# Drivers.net
KiCad netlist of a schematic drawn in Altium Designer
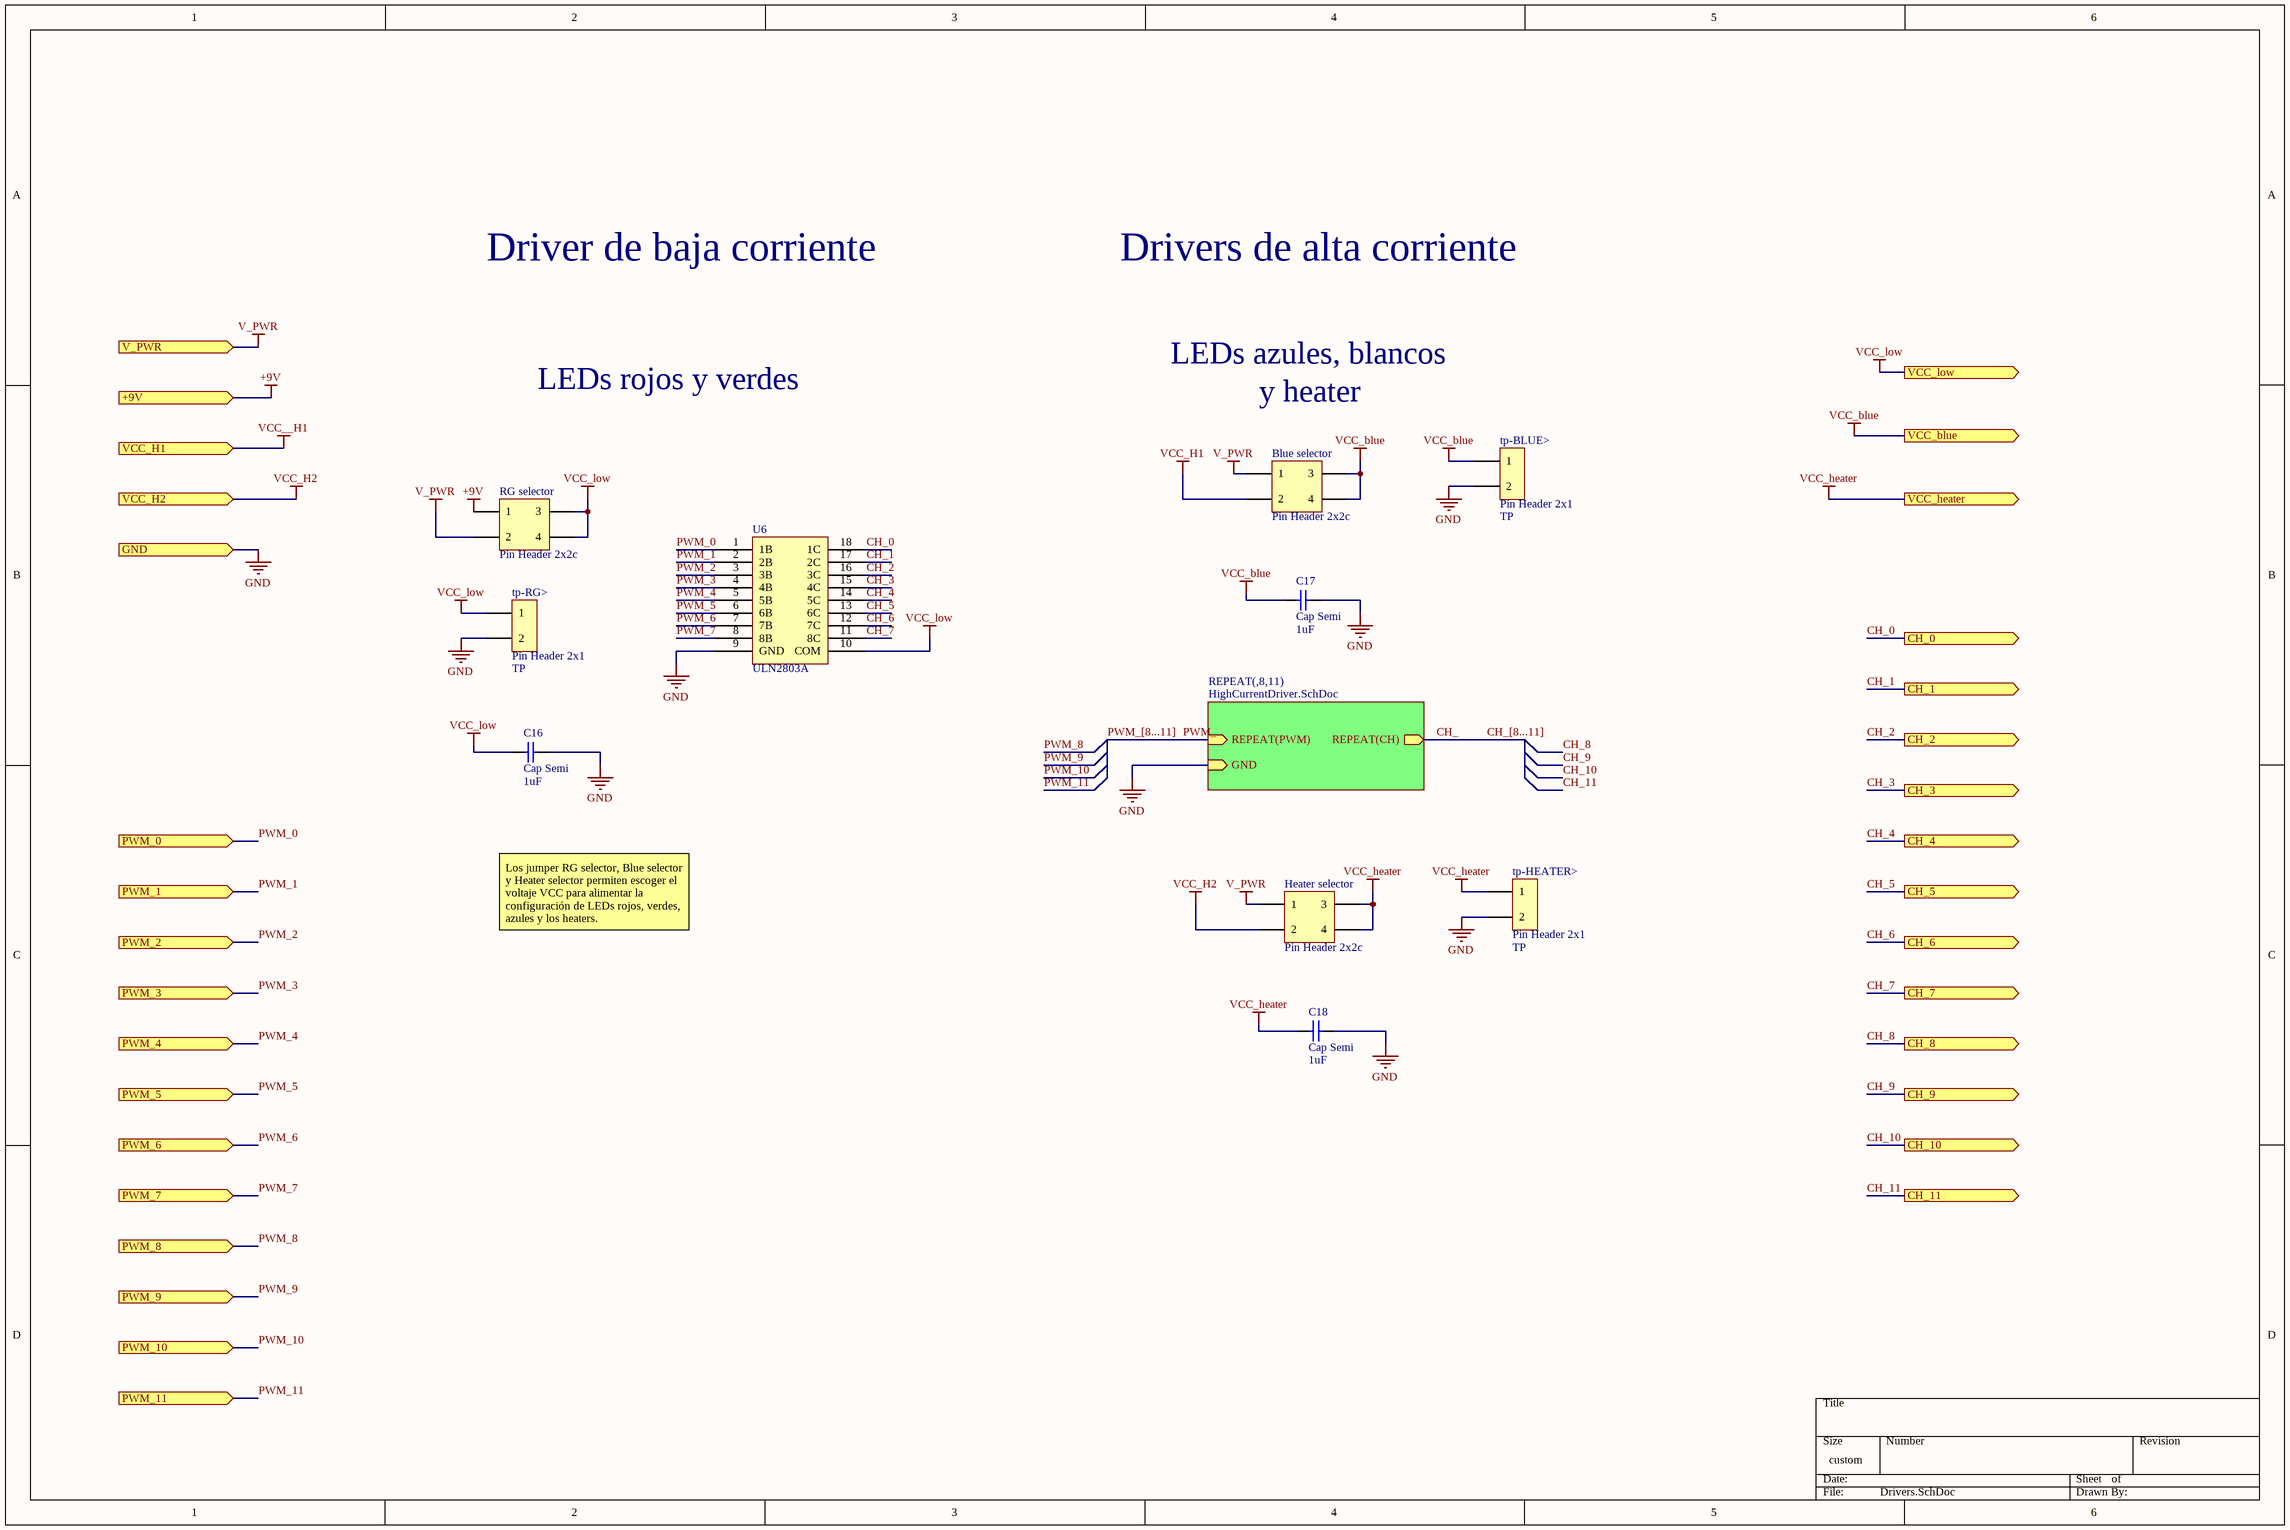
[diagram p0: Drivers.SchDoc]

(export (version "E")
  (design (tool "Eeschema 10.0.6"))
  (components
    (comp (ref "Blue selector")
      (value "Pin Header 2x2c")
      (footprint "HDR-TH_4P-P2.54-V-R2-C2-S2.54_A2541WV-2X2P")
      (description "Pin Header 4pos, 2 row, 2.54 pitch")
      (fields
        (field (name "MANUFACTURER") "CJT(Changjiang Connectors)")
        (field (name "MANUFACTURER PART NUMBER") "A2541WV-2x2P")
      )
      (libsource (lib "IoWLabsConnectors") (part "Header - 2x2c"))
    )
    (comp (ref "C16")
      (value "Cap Semi")
      (footprint "1608[0603]")
      (description "Capacitor (Semiconductor SIM Model)")
      (fields
        (field (name "ALTIUM_VALUE") "1uF")
        (field (name "MANUFACTURER") "Samsung Electro-Mechanics")
        (field (name "MANUFACTURER PART NUMBER") "CL10A105KB8NNNC")
        (field (name "PUBLISHER") "Altium Limited")
      )
      (libsource (lib "Miscellaneous Devices") (part "Cap Semi"))
    )
    (comp (ref "C17")
      (value "Cap Semi")
      (footprint "1608[0603]")
      (description "Capacitor (Semiconductor SIM Model)")
      (fields
        (field (name "ALTIUM_VALUE") "1uF")
        (field (name "MANUFACTURER") "Samsung Electro-Mechanics")
        (field (name "MANUFACTURER PART NUMBER") "CL10A105KB8NNNC")
        (field (name "PUBLISHER") "Altium Limited")
      )
      (libsource (lib "Miscellaneous Devices") (part "Cap Semi"))
    )
    (comp (ref "C18")
      (value "Cap Semi")
      (footprint "1608[0603]")
      (description "Capacitor (Semiconductor SIM Model)")
      (fields
        (field (name "ALTIUM_VALUE") "1uF")
        (field (name "MANUFACTURER") "Samsung Electro-Mechanics")
        (field (name "MANUFACTURER PART NUMBER") "CL10A105KB8NNNC")
        (field (name "PUBLISHER") "Altium Limited")
      )
      (libsource (lib "Miscellaneous Devices") (part "Cap Semi"))
    )
    (comp (ref "Heater selector")
      (value "Pin Header 2x2c")
      (footprint "HDR-TH_4P-P2.54-V-R2-C2-S2.54_A2541WV-2X2P")
      (description "Pin Header 4pos, 2 row, 2.54 pitch")
      (fields
        (field (name "MANUFACTURER") "CJT(Changjiang Connectors)")
        (field (name "MANUFACTURER PART NUMBER") "A2541WV-2x2P")
      )
      (libsource (lib "IoWLabsConnectors") (part "Header - 2x2c"))
    )
    (comp (ref "RG selector")
      (value "Pin Header 2x2c")
      (footprint "HDR-TH_4P-P2.54-V-R2-C2-S2.54_A2541WV-2X2P")
      (description "Pin Header 4pos, 2 row, 2.54 pitch")
      (fields
        (field (name "MANUFACTURER") "CJT(Changjiang Connectors)")
        (field (name "MANUFACTURER PART NUMBER") "A2541WV-2x2P")
      )
      (libsource (lib "IoWLabsConnectors") (part "Header - 2x2c"))
    )
    (comp (ref "tp-BLUE>")
      (value "Pin Header 2x1")
      (footprint "HDR-TH_P2.54-H-M_A2541WV-2P")
      (description "Pin Header 2pos, 1 row, 2.54 pitch")
      (fields
        (field (name "MANUFACTURER") "CJT(Changjiang Connectors)")
        (field (name "MANUFACTURER PART NUMBER") "A2541WV-2P")
      )
      (libsource (lib "IoWLabsConnectors") (part "Header - 2x1c"))
    )
    (comp (ref "tp-HEATER>")
      (value "Pin Header 2x1")
      (footprint "HDR-TH_P2.54-H-M_A2541WV-2P")
      (description "Pin Header 2pos, 1 row, 2.54 pitch")
      (fields
        (field (name "MANUFACTURER") "CJT(Changjiang Connectors)")
        (field (name "MANUFACTURER PART NUMBER") "A2541WV-2P")
      )
      (libsource (lib "IoWLabsConnectors") (part "Header - 2x1c"))
    )
    (comp (ref "tp-RG>")
      (value "Pin Header 2x1")
      (footprint "HDR-TH_P2.54-H-M_A2541WV-2P")
      (description "Pin Header 2pos, 1 row, 2.54 pitch")
      (fields
        (field (name "MANUFACTURER") "CJT(Changjiang Connectors)")
        (field (name "MANUFACTURER PART NUMBER") "A2541WV-2P")
      )
      (libsource (lib "IoWLabsConnectors") (part "Header - 2x1c"))
    )
    (comp (ref "U6")
      (value "ULN2803A")
      (footprint "SOIC18")
      (description "Darlington transistor array driver SOIC-18_300mi")
      (fields
        (field (name "MANUFACTURER") "Texas instrument")
        (field (name "MANUFACTURER PART NUMBER") "ULN2803ADWR")
      )
      (libsource (lib "IoWLabs") (part "ULN2803"))
    )
  )
  (nets
    (net (code "3") (name "+9V") (class "Default")
      (node (ref "RG selector") (pin "1") (pinfunction "1_1") (pintype "passive"))
    )
    (net (code "5") (name "/CH_0") (class "Default")
      (node (ref "U6") (pin "18") (pinfunction "1C_18") (pintype "passive"))
    )
    (net (code "6") (name "/CH_1") (class "Default")
      (node (ref "U6") (pin "17") (pinfunction "2C_17") (pintype "passive"))
    )
    (net (code "7") (name "/CH_2") (class "Default")
      (node (ref "U6") (pin "16") (pinfunction "3C_16") (pintype "passive"))
    )
    (net (code "8") (name "/CH_3") (class "Default")
      (node (ref "U6") (pin "15") (pinfunction "4C_15") (pintype "passive"))
    )
    (net (code "9") (name "/CH_4") (class "Default")
      (node (ref "U6") (pin "14") (pinfunction "5C_14") (pintype "passive"))
    )
    (net (code "10") (name "/CH_5") (class "Default")
      (node (ref "U6") (pin "13") (pinfunction "6C_13") (pintype "passive"))
    )
    (net (code "11") (name "/CH_6") (class "Default")
      (node (ref "U6") (pin "12") (pinfunction "7C_12") (pintype "passive"))
    )
    (net (code "12") (name "/CH_7") (class "Default")
      (node (ref "U6") (pin "11") (pinfunction "8C_11") (pintype "passive"))
    )
    (net (code "18") (name "/PWM_0") (class "Default")
      (node (ref "U6") (pin "1") (pinfunction "1B_1") (pintype "passive"))
    )
    (net (code "19") (name "/PWM_1") (class "Default")
      (node (ref "U6") (pin "2") (pinfunction "2B_2") (pintype "passive"))
    )
    (net (code "20") (name "/PWM_2") (class "Default")
      (node (ref "U6") (pin "3") (pinfunction "3B_3") (pintype "passive"))
    )
    (net (code "21") (name "/PWM_3") (class "Default")
      (node (ref "U6") (pin "4") (pinfunction "4B_4") (pintype "passive"))
    )
    (net (code "22") (name "/PWM_4") (class "Default")
      (node (ref "U6") (pin "5") (pinfunction "5B_5") (pintype "passive"))
    )
    (net (code "23") (name "/PWM_5") (class "Default")
      (node (ref "U6") (pin "6") (pinfunction "6B_6") (pintype "passive"))
    )
    (net (code "24") (name "/PWM_6") (class "Default")
      (node (ref "U6") (pin "7") (pinfunction "7B_7") (pintype "passive"))
    )
    (net (code "25") (name "/PWM_7") (class "Default")
      (node (ref "U6") (pin "8") (pinfunction "8B_8") (pintype "passive"))
    )
    (net (code "32") (name "GND") (class "Default")
      (node (ref "C16") (pin "2") (pinfunction "2_2") (pintype "passive"))
      (node (ref "C17") (pin "2") (pinfunction "2_2") (pintype "passive"))
      (node (ref "C18") (pin "2") (pinfunction "2_2") (pintype "passive"))
      (node (ref "U6") (pin "9") (pinfunction "GND_9") (pintype "passive"))
      (node (ref "tp-BLUE>") (pin "2") (pinfunction "2_2") (pintype "passive"))
      (node (ref "tp-HEATER>") (pin "2") (pinfunction "2_2") (pintype "passive"))
      (node (ref "tp-RG>") (pin "2") (pinfunction "2_2") (pintype "passive"))
    )
    (net (code "33") (name "VCC_H1") (class "Default")
      (node (ref "Blue selector") (pin "2") (pinfunction "2_2") (pintype "passive"))
    )
    (net (code "34") (name "VCC_H2") (class "Default")
      (node (ref "Heater selector") (pin "2") (pinfunction "2_2") (pintype "passive"))
    )
    (net (code "35") (name "VCC_blue") (class "Default")
      (node (ref "Blue selector") (pin "3") (pinfunction "3_3") (pintype "passive"))
      (node (ref "Blue selector") (pin "4") (pinfunction "4_4") (pintype "passive"))
      (node (ref "C17") (pin "1") (pinfunction "1_1") (pintype "passive"))
      (node (ref "tp-BLUE>") (pin "1") (pinfunction "1_1") (pintype "passive"))
    )
    (net (code "36") (name "VCC_heater") (class "Default")
      (node (ref "C18") (pin "1") (pinfunction "1_1") (pintype "passive"))
      (node (ref "Heater selector") (pin "3") (pinfunction "3_3") (pintype "passive"))
      (node (ref "Heater selector") (pin "4") (pinfunction "4_4") (pintype "passive"))
      (node (ref "tp-HEATER>") (pin "1") (pinfunction "1_1") (pintype "passive"))
    )
    (net (code "37") (name "VCC_low") (class "Default")
      (node (ref "C16") (pin "1") (pinfunction "1_1") (pintype "passive"))
      (node (ref "RG selector") (pin "3") (pinfunction "3_3") (pintype "passive"))
      (node (ref "RG selector") (pin "4") (pinfunction "4_4") (pintype "passive"))
      (node (ref "U6") (pin "10") (pinfunction "COM_10") (pintype "passive"))
      (node (ref "tp-RG>") (pin "1") (pinfunction "1_1") (pintype "passive"))
    )
    (net (code "38") (name "V_PWR") (class "Default")
      (node (ref "Blue selector") (pin "1") (pinfunction "1_1") (pintype "passive"))
      (node (ref "Heater selector") (pin "1") (pinfunction "1_1") (pintype "passive"))
      (node (ref "RG selector") (pin "2") (pinfunction "2_2") (pintype "passive"))
    )
  )
)
